# Sheet1.net
KiCad netlist of a schematic drawn in Altium Designer
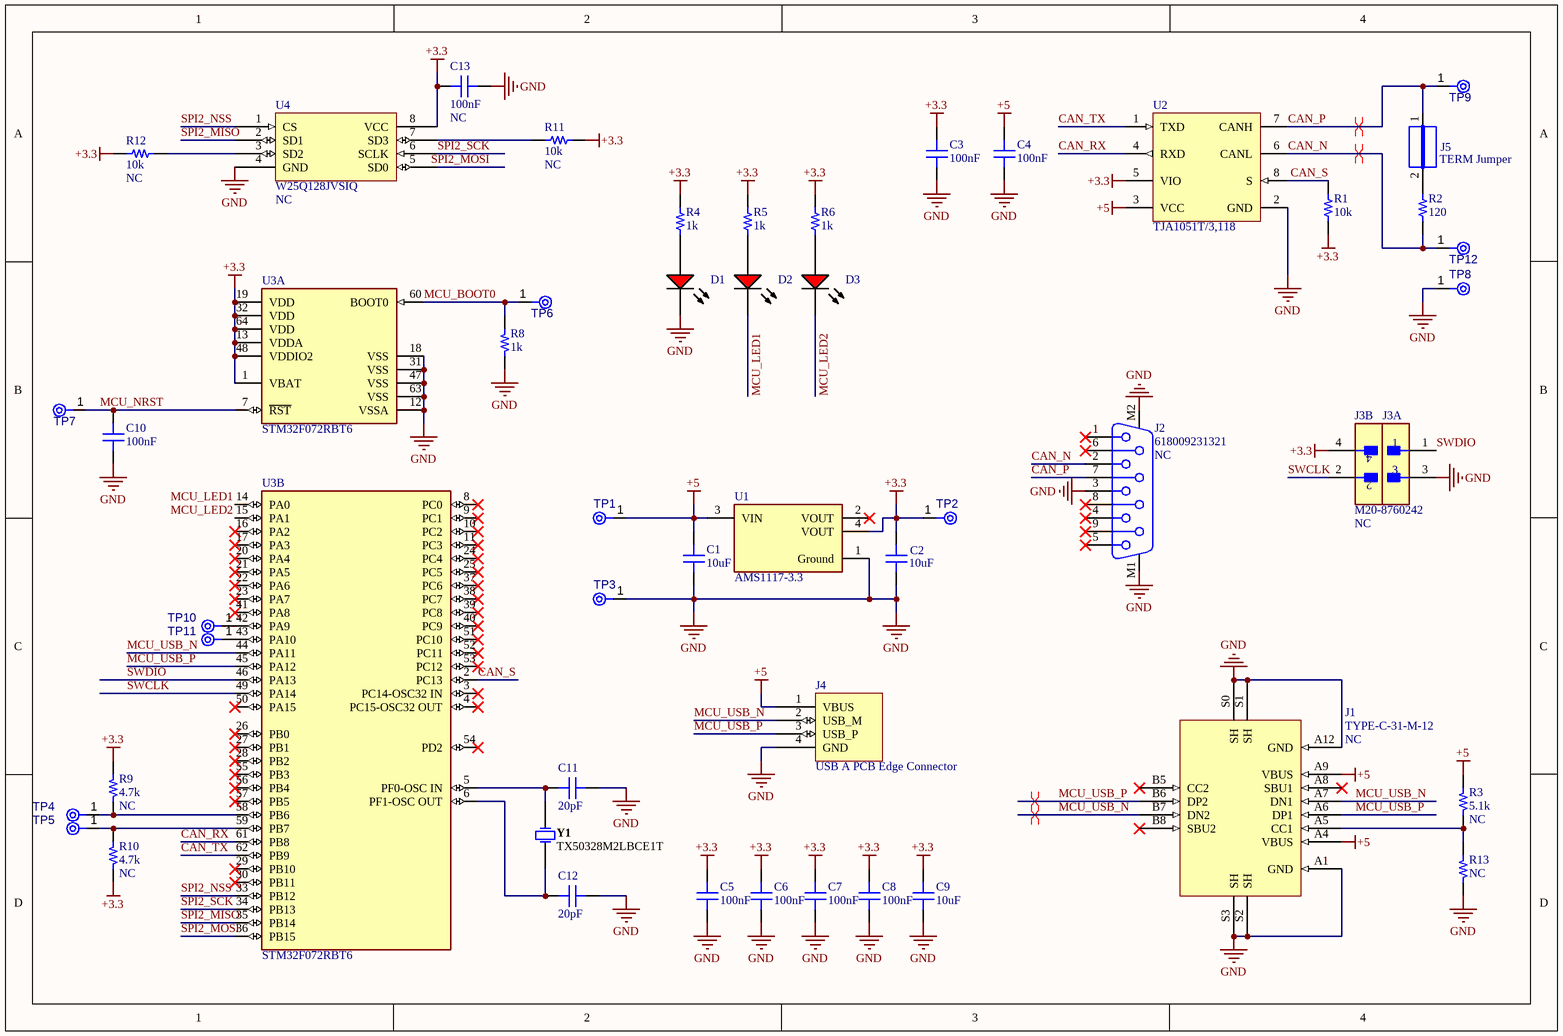
[diagram p0: Sheet1.SchDoc]

(export (version "E")
  (design (tool "Eeschema 10.0.6"))
  (components
    (comp (ref "C1")
      (value "10uF")
      (footprint "CAPC0603(1608)100_L")
      (description "Generic Capacitor")
      (fields (field (name "Comment") "Capacitor"))
      (libsource (lib "OTH Regensburg Ostbayerische Technische Hochschule Regensburg") (part "CAPACITOR"))
    )
    (comp (ref "C2")
      (value "10uF")
      (footprint "CAPC0603(1608)100_L")
      (description "Generic Capacitor")
      (fields (field (name "Comment") "Capacitor"))
      (libsource (lib "OTH Regensburg Ostbayerische Technische Hochschule Regensburg") (part "CAPACITOR"))
    )
    (comp (ref "C3")
      (value "100nF")
      (footprint "CAPC0402(1005)33_L")
      (description "Generic Capacitor")
      (fields (field (name "Comment") "Capacitor"))
      (libsource (lib "OTH Regensburg Ostbayerische Technische Hochschule Regensburg") (part "CAPACITOR"))
    )
    (comp (ref "C4")
      (value "100nF")
      (footprint "CAPC0402(1005)33_L")
      (description "Generic Capacitor")
      (fields (field (name "Comment") "Capacitor"))
      (libsource (lib "OTH Regensburg Ostbayerische Technische Hochschule Regensburg") (part "CAPACITOR"))
    )
    (comp (ref "C5")
      (value "100nF")
      (footprint "CAPC0402(1005)33_L")
      (description "Generic Capacitor")
      (fields (field (name "Comment") "Capacitor"))
      (libsource (lib "OTH Regensburg Ostbayerische Technische Hochschule Regensburg") (part "CAPACITOR"))
    )
    (comp (ref "C6")
      (value "100nF")
      (footprint "CAPC0402(1005)33_L")
      (description "Generic Capacitor")
      (fields (field (name "Comment") "Capacitor"))
      (libsource (lib "OTH Regensburg Ostbayerische Technische Hochschule Regensburg") (part "CAPACITOR"))
    )
    (comp (ref "C7")
      (value "100nF")
      (footprint "CAPC0402(1005)33_L")
      (description "Generic Capacitor")
      (fields (field (name "Comment") "Capacitor"))
      (libsource (lib "OTH Regensburg Ostbayerische Technische Hochschule Regensburg") (part "CAPACITOR"))
    )
    (comp (ref "C8")
      (value "100nF")
      (footprint "CAPC0402(1005)33_L")
      (description "Generic Capacitor")
      (fields (field (name "Comment") "Capacitor"))
      (libsource (lib "OTH Regensburg Ostbayerische Technische Hochschule Regensburg") (part "CAPACITOR"))
    )
    (comp (ref "C9")
      (value "10uF")
      (footprint "CAPC0603(1608)100_L")
      (description "Generic Capacitor")
      (fields (field (name "Comment") "Capacitor"))
      (libsource (lib "OTH Regensburg Ostbayerische Technische Hochschule Regensburg") (part "CAPACITOR"))
    )
    (comp (ref "C10")
      (value "100nF")
      (footprint "CAPC0402(1005)33_L")
      (description "Generic Capacitor")
      (fields (field (name "Comment") "Capacitor"))
      (libsource (lib "OTH Regensburg Ostbayerische Technische Hochschule Regensburg") (part "CAPACITOR"))
    )
    (comp (ref "C11")
      (value "20pF")
      (footprint "CAPC0402(1005)33_L")
      (description "Generic Capacitor")
      (fields (field (name "Comment") "Capacitor"))
      (libsource (lib "OTH Regensburg Ostbayerische Technische Hochschule Regensburg") (part "CAPACITOR"))
    )
    (comp (ref "C12")
      (value "20pF")
      (footprint "CAPC0402(1005)33_L")
      (description "Generic Capacitor")
      (fields (field (name "Comment") "Capacitor"))
      (libsource (lib "OTH Regensburg Ostbayerische Technische Hochschule Regensburg") (part "CAPACITOR"))
    )
    (comp (ref "C13")
      (value "100nF")
      (footprint "CAPC0402(1005)33_L")
      (description "Generic Capacitor")
      (fields (field (name "NOT POPULATED") "NC") (field (name "Comment") "Capacitor"))
      (libsource (lib "OTH Regensburg Ostbayerische Technische Hochschule Regensburg") (part "CAPACITOR"))
    )
    (comp (ref "D1")
      (value "TLMS1100-GS08")
      (footprint "VISH-TLMX1100_V")
      (description "LED, RED, 2.1 V, -40 to 100 degC, 2-Pin SMD (0603), RoHS, Tape and Reel")
      (fields (field (name "TOLERANCE") "5%"))
      (libsource (lib "Altium Content Vault") (part "LED-RED-AK-2"))
    )
    (comp (ref "D2")
      (value "TLMS1100-GS08")
      (footprint "VISH-TLMX1100_V")
      (description "LED, RED, 2.1 V, -40 to 100 degC, 2-Pin SMD (0603), RoHS, Tape and Reel")
      (fields (field (name "TOLERANCE") "5%"))
      (libsource (lib "Altium Content Vault") (part "LED-RED-AK-2"))
    )
    (comp (ref "D3")
      (value "TLMS1100-GS08")
      (footprint "VISH-TLMX1100_V")
      (description "LED, RED, 2.1 V, -40 to 100 degC, 2-Pin SMD (0603), RoHS, Tape and Reel")
      (fields (field (name "TOLERANCE") "5%"))
      (libsource (lib "Altium Content Vault") (part "LED-RED-AK-2"))
    )
    (comp (ref "J1")
      (value "TYPE-C-31-M-12")
      (footprint "TYPE-C-31-M-12-Footprint-1")
      (description "USB Type C USB 2.0")
      (fields (field (name "NOT POPULATED") "NC"))
      (libsource (lib "OTH Regensburg Ostbayerische Technische Hochschule Regensburg") (part "TYPE-C-31-M-12-Symbol-1"))
    )
    (comp (ref "J2")
      (value "618009231321")
      (footprint "618009231321")
      (fields (field (name "NOT POPULATED") "NC"))
      (libsource (lib "Altium Content Vault") (part "D-Sub_Female_09p"))
    )
    (comp (ref "J3")
      (value "M20-8760242")
      (footprint "FP-M20-8760242-MFG")
      (description "CONN HEADER SMD 4POS 2.54MM")
      (fields (field (name "NOT POPULATED") "NC"))
      (libsource (lib "Altium Content Vault") (part "1621473add15499e993d6bbd36d0f06"))
    )
    (comp (ref "J4")
      (value "USB A PCB Edge Connector")
      (footprint "USB A PCB Edge Connector-Footprint-1")
      (libsource (lib "OTH Regensburg Ostbayerische Technische Hochschule Regensburg") (part "USB A PCB Edge Connector-Symbol-1"))
    )
    (comp (ref "J5")
      (value "JUMPER")
      (footprint "JUMPER")
      (fields (field (name "NOT POPULATED") "TERM Jumper"))
      (libsource (lib "OTH Regensburg Ostbayerische Technische Hochschule Regensburg") (part "JUMPER"))
    )
    (comp (ref "R1")
      (value "10k")
      (footprint "RESC0402(1005)_L")
      (description "Generic Resistor")
      (fields (field (name "Comment") "Resistor"))
      (libsource (lib "OTH Regensburg Ostbayerische Technische Hochschule Regensburg") (part "RESISTOR"))
    )
    (comp (ref "R2")
      (value "120")
      (footprint "RESC0603(1608)_L")
      (description "Generic Resistor")
      (fields (field (name "Comment") "Resistor"))
      (libsource (lib "OTH Regensburg Ostbayerische Technische Hochschule Regensburg") (part "RESISTOR"))
    )
    (comp (ref "R3")
      (value "5.1k")
      (footprint "RESC0603(1608)_L")
      (description "Generic Resistor")
      (fields (field (name "NOT POPULATED") "NC") (field (name "Comment") "Resistor"))
      (libsource (lib "OTH Regensburg Ostbayerische Technische Hochschule Regensburg") (part "RESISTOR"))
    )
    (comp (ref "R4")
      (value "1k")
      (footprint "RESC0402(1005)_L")
      (description "Generic Resistor")
      (fields (field (name "Comment") "Resistor"))
      (libsource (lib "OTH Regensburg Ostbayerische Technische Hochschule Regensburg") (part "RESISTOR"))
    )
    (comp (ref "R5")
      (value "1k")
      (footprint "RESC0402(1005)_L")
      (description "Generic Resistor")
      (fields (field (name "Comment") "Resistor"))
      (libsource (lib "OTH Regensburg Ostbayerische Technische Hochschule Regensburg") (part "RESISTOR"))
    )
    (comp (ref "R6")
      (value "1k")
      (footprint "RESC0402(1005)_L")
      (description "Generic Resistor")
      (fields (field (name "Comment") "Resistor"))
      (libsource (lib "OTH Regensburg Ostbayerische Technische Hochschule Regensburg") (part "RESISTOR"))
    )
    (comp (ref "R8")
      (value "1k")
      (footprint "RESC0402(1005)_L")
      (description "Generic Resistor")
      (fields (field (name "Comment") "Resistor"))
      (libsource (lib "OTH Regensburg Ostbayerische Technische Hochschule Regensburg") (part "RESISTOR"))
    )
    (comp (ref "R9")
      (value "4.7k")
      (footprint "RESC0603(1608)_L")
      (description "Generic Resistor")
      (fields (field (name "NOT POPULATED") "NC") (field (name "Comment") "Resistor"))
      (libsource (lib "OTH Regensburg Ostbayerische Technische Hochschule Regensburg") (part "RESISTOR"))
    )
    (comp (ref "R10")
      (value "4.7k")
      (footprint "RESC0603(1608)_L")
      (description "Generic Resistor")
      (fields (field (name "NOT POPULATED") "NC") (field (name "Comment") "Resistor"))
      (libsource (lib "OTH Regensburg Ostbayerische Technische Hochschule Regensburg") (part "RESISTOR"))
    )
    (comp (ref "R11")
      (value "10k")
      (footprint "RESC0402(1005)_L")
      (description "Generic Resistor")
      (fields (field (name "NOT POPULATED") "NC") (field (name "Comment") "Resistor"))
      (libsource (lib "OTH Regensburg Ostbayerische Technische Hochschule Regensburg") (part "RESISTOR"))
    )
    (comp (ref "R12")
      (value "10k")
      (footprint "RESC0402(1005)_L")
      (description "Generic Resistor")
      (fields (field (name "NOT POPULATED") "NC") (field (name "Comment") "Resistor"))
      (libsource (lib "OTH Regensburg Ostbayerische Technische Hochschule Regensburg") (part "RESISTOR"))
    )
    (comp (ref "R13")
      (value "Resistor")
      (footprint "RESC0603(1608)_L")
      (description "Generic Resistor")
      (fields (field (name "NOT POPULATED") "NC"))
      (libsource (lib "OTH Regensburg Ostbayerische Technische Hochschule Regensburg") (part "RESISTOR"))
    )
    (comp (ref "TP1")
      (value "Test Point")
      (footprint "New footprint 1")
      (libsource (lib "OTH Regensburg Ostbayerische Technische Hochschule Regensburg") (part "CMP-001-0001-4"))
    )
    (comp (ref "TP2")
      (value "Test Point")
      (footprint "New footprint 1")
      (libsource (lib "OTH Regensburg Ostbayerische Technische Hochschule Regensburg") (part "CMP-001-0001-4"))
    )
    (comp (ref "TP3")
      (value "Test Point")
      (footprint "New footprint 1")
      (libsource (lib "OTH Regensburg Ostbayerische Technische Hochschule Regensburg") (part "CMP-001-0001-4"))
    )
    (comp (ref "TP4")
      (value "Test Point")
      (footprint "New footprint 1")
      (libsource (lib "OTH Regensburg Ostbayerische Technische Hochschule Regensburg") (part "CMP-001-0001-4"))
    )
    (comp (ref "TP5")
      (value "Test Point")
      (footprint "New footprint 1")
      (libsource (lib "OTH Regensburg Ostbayerische Technische Hochschule Regensburg") (part "CMP-001-0001-4"))
    )
    (comp (ref "TP6")
      (value "Test Point")
      (footprint "New footprint 1")
      (libsource (lib "OTH Regensburg Ostbayerische Technische Hochschule Regensburg") (part "CMP-001-0001-4"))
    )
    (comp (ref "TP7")
      (value "Test Point")
      (footprint "New footprint 1")
      (libsource (lib "OTH Regensburg Ostbayerische Technische Hochschule Regensburg") (part "CMP-001-0001-4"))
    )
    (comp (ref "TP8")
      (value "Test Point")
      (footprint "New footprint 1")
      (libsource (lib "OTH Regensburg Ostbayerische Technische Hochschule Regensburg") (part "CMP-001-0001-4"))
    )
    (comp (ref "TP9")
      (value "Test Point")
      (footprint "New footprint 1")
      (libsource (lib "OTH Regensburg Ostbayerische Technische Hochschule Regensburg") (part "CMP-001-0001-4"))
    )
    (comp (ref "TP10")
      (value "Test Point")
      (footprint "New footprint 1")
      (libsource (lib "OTH Regensburg Ostbayerische Technische Hochschule Regensburg") (part "CMP-001-0001-4"))
    )
    (comp (ref "TP11")
      (value "Test Point")
      (footprint "New footprint 1")
      (libsource (lib "OTH Regensburg Ostbayerische Technische Hochschule Regensburg") (part "CMP-001-0001-4"))
    )
    (comp (ref "TP12")
      (value "Test Point")
      (footprint "New footprint 1")
      (libsource (lib "OTH Regensburg Ostbayerische Technische Hochschule Regensburg") (part "CMP-001-0001-4"))
    )
    (comp (ref "U1")
      (value "AMS1117-3.3")
      (footprint "FP-AMS1117-IPC_A")
      (description "LDO Voltage Regulators 1A, 3.3V")
      (fields
        (field (name "OCTOPART") "https://octopart.com/ams1117-3.3-advanced+monolithic+systems-25899300")
        (field (name "MANUFACTURER") "Advanced Monolithic Systems")
      )
      (libsource (lib "Altium Content Vault") (part "8bdbb5f8e77002000e30dd2845d0354"))
    )
    (comp (ref "U2")
      (value "TJA1051T/3,118")
      (footprint "NXP-SOIC-8_L")
      (description "High-Speed CAN Transceiver, 3 to 5 V, 8-Pin SOIC (SOT96-1), RoHS, Tape and Reel")
      (fields (field (name "MANUFACTURER") "NXP"))
      (libsource (lib "Altium Content Vault") (part "NXP-TJA1051T_3-SOIC-8"))
    )
    (comp (ref "U3")
      (value "STM32F072RBT6")
      (footprint "FP-LQFP64-5W-MFG")
      (description "IC MCU 32BIT 128KB FLASH 64LQFP")
      (fields
        (field (name "MANUFACTURER") "STMicroelectronics")
        (field (name "OCTOPART") "https://octopart.com/stm32f072rbt6-stmicroelectronics-34084849")
      )
      (libsource (lib "Altium Content Vault") (part "2898ff2af3f565795d3b9648bb0e0e1"))
    )
    (comp (ref "U4")
      (value "W25Q128JVSIQ")
      (footprint "WINBOND SOIC-8 208MIL WIDE")
      (description "Flash, 16MX8, PDSO8")
      (fields (field (name "NOT POPULATED") "NC"))
      (libsource (lib "OTH Regensburg Ostbayerische Technische Hochschule Regensburg") (part "W25Q128JVSIQ-Symbol-1"))
    )
    (comp (ref "Y1")
      (value "TX50328M2LBCE1T")
      (footprint "FP-ABM3-MFG")
      (libsource (lib "OTH Regensburg Ostbayerische Technische Hochschule Regensburg") (part "XTAL-2"))
    )
  )
  (nets
    (net (code "1") (name "+3.3") (class "Default")
      (node (ref "C13") (pin "2") (pinfunction "2_2") (pintype "passive"))
      (node (ref "C2") (pin "2") (pinfunction "2_2") (pintype "passive"))
      (node (ref "C3") (pin "2") (pinfunction "2_2") (pintype "passive"))
      (node (ref "C5") (pin "2") (pinfunction "2_2") (pintype "passive"))
      (node (ref "C6") (pin "2") (pinfunction "2_2") (pintype "passive"))
      (node (ref "C7") (pin "2") (pinfunction "2_2") (pintype "passive"))
      (node (ref "C8") (pin "2") (pinfunction "2_2") (pintype "passive"))
      (node (ref "C9") (pin "2") (pinfunction "2_2") (pintype "passive"))
      (node (ref "J3") (pin "4") (pinfunction "4_4") (pintype "passive"))
      (node (ref "R1") (pin "2") (pinfunction "2_2") (pintype "passive"))
      (node (ref "R10") (pin "1") (pinfunction "1_1") (pintype "passive"))
      (node (ref "R11") (pin "2") (pinfunction "2_2") (pintype "passive"))
      (node (ref "R12") (pin "1") (pinfunction "1_1") (pintype "passive"))
      (node (ref "R4") (pin "2") (pinfunction "2_2") (pintype "passive"))
      (node (ref "R5") (pin "2") (pinfunction "2_2") (pintype "passive"))
      (node (ref "R6") (pin "2") (pinfunction "2_2") (pintype "passive"))
      (node (ref "R9") (pin "2") (pinfunction "2_2") (pintype "passive"))
      (node (ref "TP2") (pin "1") (pinfunction "TP_1") (pintype "passive"))
      (node (ref "U1") (pin "4") (pinfunction "VOUT_4") (pintype "passive"))
      (node (ref "U2") (pin "5") (pinfunction "VIO_5") (pintype "power_in"))
      (node (ref "U3") (pin "1") (pinfunction "VBAT_1") (pintype "power_in"))
      (node (ref "U3") (pin "13") (pinfunction "VDDA_13") (pintype "power_in"))
      (node (ref "U3") (pin "19") (pinfunction "VDD_19") (pintype "power_in"))
      (node (ref "U3") (pin "32") (pinfunction "VDD_32") (pintype "power_in"))
      (node (ref "U3") (pin "48") (pinfunction "VDDIO2_48") (pintype "power_in"))
      (node (ref "U3") (pin "64") (pinfunction "VDD_64") (pintype "power_in"))
      (node (ref "U4") (pin "8") (pinfunction "VCC_8") (pintype "power_in"))
    )
    (net (code "2") (name "+5") (class "Default")
      (node (ref "C1") (pin "2") (pinfunction "2_2") (pintype "passive"))
      (node (ref "C4") (pin "2") (pinfunction "2_2") (pintype "passive"))
      (node (ref "J1") (pin "A4") (pinfunction "VBUS_A4") (pintype "input"))
      (node (ref "J1") (pin "A9") (pinfunction "VBUS_A9") (pintype "input"))
      (node (ref "J4") (pin "1") (pinfunction "VBUS_1") (pintype "power_in"))
      (node (ref "R3") (pin "1") (pinfunction "1_1") (pintype "passive"))
      (node (ref "TP1") (pin "1") (pinfunction "TP_1") (pintype "passive"))
      (node (ref "U1") (pin "3") (pinfunction "VIN_3") (pintype "power_in"))
      (node (ref "U2") (pin "3") (pinfunction "VCC_3") (pintype "power_in"))
    )
    (net (code "3") (name "/CAN_N") (class "Default")
      (node (ref "J2") (pin "2") (pinfunction "2_2") (pintype "passive"))
      (node (ref "R2") (pin "2") (pinfunction "2_2") (pintype "passive"))
      (node (ref "TP12") (pin "1") (pinfunction "TP_1") (pintype "passive"))
      (node (ref "U2") (pin "6") (pinfunction "CANL_6") (pintype "passive"))
    )
    (net (code "4") (name "/CAN_P") (class "Default")
      (node (ref "J2") (pin "7") (pinfunction "7_7") (pintype "passive"))
      (node (ref "J5") (pin "1") (pinfunction "1_1") (pintype "passive"))
      (node (ref "TP9") (pin "1") (pinfunction "TP_1") (pintype "passive"))
      (node (ref "U2") (pin "7") (pinfunction "CANH_7") (pintype "passive"))
    )
    (net (code "5") (name "/CAN_RX") (class "Default")
      (node (ref "U2") (pin "4") (pinfunction "RXD_4") (pintype "output"))
      (node (ref "U3") (pin "61") (pinfunction "PB8_61") (pintype "bidirectional"))
    )
    (net (code "6") (name "/CAN_S") (class "Default")
      (node (ref "R1") (pin "1") (pinfunction "1_1") (pintype "passive"))
      (node (ref "U2") (pin "8") (pinfunction "S_8") (pintype "input"))
      (node (ref "U3") (pin "2") (pinfunction "PC13_2") (pintype "bidirectional"))
    )
    (net (code "7") (name "/CAN_TX") (class "Default")
      (node (ref "U2") (pin "1") (pinfunction "TXD_1") (pintype "input"))
      (node (ref "U3") (pin "62") (pinfunction "PB9_62") (pintype "bidirectional"))
    )
    (net (code "8") (name "/MCU_BOOT0") (class "Default")
      (node (ref "R8") (pin "2") (pinfunction "2_2") (pintype "passive"))
      (node (ref "TP6") (pin "1") (pinfunction "TP_1") (pintype "passive"))
      (node (ref "U3") (pin "60") (pinfunction "BOOT0_60") (pintype "input"))
    )
    (net (code "9") (name "/MCU_LED1") (class "Default")
      (node (ref "D2") (pin "2") (pinfunction "K_2") (pintype "passive"))
      (node (ref "U3") (pin "14") (pinfunction "PA0_14") (pintype "bidirectional"))
    )
    (net (code "10") (name "/MCU_LED2") (class "Default")
      (node (ref "D3") (pin "2") (pinfunction "K_2") (pintype "passive"))
      (node (ref "U3") (pin "15") (pinfunction "PA1_15") (pintype "bidirectional"))
    )
    (net (code "11") (name "/MCU_NRST") (class "Default")
      (node (ref "C10") (pin "2") (pinfunction "2_2") (pintype "passive"))
      (node (ref "TP7") (pin "1") (pinfunction "TP_1") (pintype "passive"))
      (node (ref "U3") (pin "7") (pinfunction "~{RST}_7") (pintype "bidirectional"))
    )
    (net (code "12") (name "/MCU_USB_N") (class "Default")
      (node (ref "J1") (pin "A7") (pinfunction "DN1_A7") (pintype "input"))
      (node (ref "J1") (pin "B7") (pinfunction "DN2_B7") (pintype "input"))
      (node (ref "J4") (pin "2") (pinfunction "USB_M_2") (pintype "bidirectional"))
      (node (ref "U3") (pin "44") (pinfunction "PA11_44") (pintype "bidirectional"))
    )
    (net (code "13") (name "/MCU_USB_P") (class "Default")
      (node (ref "J1") (pin "A6") (pinfunction "DP1_A6") (pintype "input"))
      (node (ref "J1") (pin "B6") (pinfunction "DP2_B6") (pintype "input"))
      (node (ref "J4") (pin "3") (pinfunction "USB_P_3") (pintype "bidirectional"))
      (node (ref "U3") (pin "45") (pinfunction "PA12_45") (pintype "bidirectional"))
    )
    (net (code "14") (name "/SPI2_MISO") (class "Default")
      (node (ref "U3") (pin "35") (pinfunction "PB14_35") (pintype "bidirectional"))
      (node (ref "U4") (pin "2") (pinfunction "SD1_2") (pintype "bidirectional"))
    )
    (net (code "15") (name "/SPI2_MOSI") (class "Default")
      (node (ref "U3") (pin "36") (pinfunction "PB15_36") (pintype "bidirectional"))
      (node (ref "U4") (pin "5") (pinfunction "SD0_5") (pintype "bidirectional"))
    )
    (net (code "16") (name "/SPI2_NSS") (class "Default")
      (node (ref "U3") (pin "33") (pinfunction "PB12_33") (pintype "bidirectional"))
      (node (ref "U4") (pin "1") (pinfunction "CS_1") (pintype "input"))
    )
    (net (code "17") (name "/SPI2_SCK") (class "Default")
      (node (ref "U3") (pin "34") (pinfunction "PB13_34") (pintype "bidirectional"))
      (node (ref "U4") (pin "6") (pinfunction "SCLK_6") (pintype "input"))
    )
    (net (code "18") (name "/SWCLK") (class "Default")
      (node (ref "J3") (pin "2") (pinfunction "2_2") (pintype "passive"))
      (node (ref "U3") (pin "49") (pinfunction "PA14_49") (pintype "bidirectional"))
    )
    (net (code "19") (name "/SWDIO") (class "Default")
      (node (ref "J3") (pin "1") (pinfunction "1_1") (pintype "passive"))
      (node (ref "U3") (pin "46") (pinfunction "PA13_46") (pintype "bidirectional"))
    )
    (net (code "20") (name "GND") (class "Default")
      (node (ref "C1") (pin "1") (pinfunction "1_1") (pintype "passive"))
      (node (ref "C10") (pin "1") (pinfunction "1_1") (pintype "passive"))
      (node (ref "C11") (pin "1") (pinfunction "1_1") (pintype "passive"))
      (node (ref "C12") (pin "1") (pinfunction "1_1") (pintype "passive"))
      (node (ref "C13") (pin "1") (pinfunction "1_1") (pintype "passive"))
      (node (ref "C2") (pin "1") (pinfunction "1_1") (pintype "passive"))
      (node (ref "C3") (pin "1") (pinfunction "1_1") (pintype "passive"))
      (node (ref "C4") (pin "1") (pinfunction "1_1") (pintype "passive"))
      (node (ref "C5") (pin "1") (pinfunction "1_1") (pintype "passive"))
      (node (ref "C6") (pin "1") (pinfunction "1_1") (pintype "passive"))
      (node (ref "C7") (pin "1") (pinfunction "1_1") (pintype "passive"))
      (node (ref "C8") (pin "1") (pinfunction "1_1") (pintype "passive"))
      (node (ref "C9") (pin "1") (pinfunction "1_1") (pintype "passive"))
      (node (ref "D1") (pin "2") (pinfunction "K_2") (pintype "passive"))
      (node (ref "J1") (pin "A1") (pinfunction "GND_A1") (pintype "input"))
      (node (ref "J1") (pin "A12") (pinfunction "GND_A12") (pintype "input"))
      (node (ref "J1") (pin "S0") (pinfunction "SH_S0") (pintype "passive"))
      (node (ref "J1") (pin "S1") (pinfunction "SH_S1") (pintype "passive"))
      (node (ref "J1") (pin "S2") (pinfunction "SH_S2") (pintype "passive"))
      (node (ref "J1") (pin "S3") (pinfunction "SH_S3") (pintype "passive"))
      (node (ref "J2") (pin "3") (pinfunction "3_3") (pintype "passive"))
      (node (ref "J2") (pin "M1") (pinfunction "M1_M1") (pintype "passive"))
      (node (ref "J2") (pin "M2") (pinfunction "M2_M2") (pintype "passive"))
      (node (ref "J3") (pin "3") (pinfunction "3_3") (pintype "passive"))
      (node (ref "J4") (pin "4") (pinfunction "GND_4") (pintype "power_in"))
      (node (ref "R13") (pin "1") (pinfunction "1_1") (pintype "passive"))
      (node (ref "R8") (pin "1") (pinfunction "1_1") (pintype "passive"))
      (node (ref "TP3") (pin "1") (pinfunction "TP_1") (pintype "passive"))
      (node (ref "TP8") (pin "1") (pinfunction "TP_1") (pintype "passive"))
      (node (ref "U1") (pin "1") (pinfunction "Ground_1") (pintype "power_in"))
      (node (ref "U2") (pin "2") (pinfunction "GND_2") (pintype "power_in"))
      (node (ref "U3") (pin "12") (pinfunction "VSSA_12") (pintype "power_in"))
      (node (ref "U3") (pin "18") (pinfunction "VSS_18") (pintype "power_in"))
      (node (ref "U3") (pin "31") (pinfunction "VSS_31") (pintype "power_in"))
      (node (ref "U3") (pin "47") (pinfunction "VSS_47") (pintype "power_in"))
      (node (ref "U3") (pin "63") (pinfunction "VSS_63") (pintype "power_in"))
      (node (ref "U4") (pin "4") (pinfunction "GND_4") (pintype "power_in"))
    )
    (net (code "21") (name "Net-(D1-A)") (class "Default")
      (node (ref "D1") (pin "1") (pinfunction "A_1") (pintype "passive"))
      (node (ref "R4") (pin "1") (pinfunction "1_1") (pintype "passive"))
    )
    (net (code "22") (name "Net-(D2-A)") (class "Default")
      (node (ref "D2") (pin "1") (pinfunction "A_1") (pintype "passive"))
      (node (ref "R5") (pin "1") (pinfunction "1_1") (pintype "passive"))
    )
    (net (code "23") (name "Net-(D3-A)") (class "Default")
      (node (ref "D3") (pin "1") (pinfunction "A_1") (pintype "passive"))
      (node (ref "R6") (pin "1") (pinfunction "1_1") (pintype "passive"))
    )
    (net (code "24") (name "Net-(J1-CC1)") (class "Default")
      (node (ref "J1") (pin "A5") (pinfunction "CC1_A5") (pintype "input"))
      (node (ref "R13") (pin "2") (pinfunction "2_2") (pintype "passive"))
      (node (ref "R3") (pin "2") (pinfunction "2_2") (pintype "passive"))
    )
    (net (code "25") (name "Net-(J5-Pad2)") (class "Default")
      (node (ref "J5") (pin "2") (pinfunction "2_2") (pintype "passive"))
      (node (ref "R2") (pin "1") (pinfunction "1_1") (pintype "passive"))
    )
    (net (code "26") (name "Net-(TP4-TP)") (class "Default")
      (node (ref "R9") (pin "1") (pinfunction "1_1") (pintype "passive"))
      (node (ref "TP4") (pin "1") (pinfunction "TP_1") (pintype "passive"))
      (node (ref "U3") (pin "58") (pinfunction "PB6_58") (pintype "bidirectional"))
    )
    (net (code "27") (name "Net-(TP5-TP)") (class "Default")
      (node (ref "R10") (pin "2") (pinfunction "2_2") (pintype "passive"))
      (node (ref "TP5") (pin "1") (pinfunction "TP_1") (pintype "passive"))
      (node (ref "U3") (pin "59") (pinfunction "PB7_59") (pintype "bidirectional"))
    )
    (net (code "28") (name "Net-(TP10-TP)") (class "Default")
      (node (ref "TP10") (pin "1") (pinfunction "TP_1") (pintype "passive"))
      (node (ref "U3") (pin "42") (pinfunction "PA9_42") (pintype "bidirectional"))
    )
    (net (code "29") (name "Net-(TP11-TP)") (class "Default")
      (node (ref "TP11") (pin "1") (pinfunction "TP_1") (pintype "passive"))
      (node (ref "U3") (pin "43") (pinfunction "PA10_43") (pintype "bidirectional"))
    )
    (net (code "30") (name "Net-(U3B-PF0-OSC_IN)") (class "Default")
      (node (ref "C11") (pin "2") (pinfunction "2_2") (pintype "passive"))
      (node (ref "U3") (pin "5") (pinfunction "PF0-OSC_IN_5") (pintype "bidirectional"))
      (node (ref "Y1") (pin "2") (pinfunction "2_2") (pintype "passive"))
    )
    (net (code "31") (name "Net-(U3B-PF1-OSC_OUT)") (class "Default")
      (node (ref "C12") (pin "2") (pinfunction "2_2") (pintype "passive"))
      (node (ref "U3") (pin "6") (pinfunction "PF1-OSC_OUT_6") (pintype "bidirectional"))
      (node (ref "Y1") (pin "1") (pinfunction "1_1") (pintype "passive"))
    )
    (net (code "32") (name "Net-(U4-SD2)") (class "Default")
      (node (ref "R12") (pin "2") (pinfunction "2_2") (pintype "passive"))
      (node (ref "U4") (pin "3") (pinfunction "SD2_3") (pintype "bidirectional"))
    )
    (net (code "33") (name "Net-(U4-SD3)") (class "Default")
      (node (ref "R11") (pin "1") (pinfunction "1_1") (pintype "passive"))
      (node (ref "U4") (pin "7") (pinfunction "SD3_7") (pintype "bidirectional"))
    )
    (net (code "34") (name "unconnected-(J1-CC2-PadB5)") (class "Default")
      (node (ref "J1") (pin "B5") (pinfunction "CC2_B5") (pintype "input+no_connect"))
    )
    (net (code "35") (name "unconnected-(J1-SBU1-PadA8)") (class "Default")
      (node (ref "J1") (pin "A8") (pinfunction "SBU1_A8") (pintype "input+no_connect"))
    )
    (net (code "36") (name "unconnected-(J1-SBU2-PadB8)") (class "Default")
      (node (ref "J1") (pin "B8") (pinfunction "SBU2_B8") (pintype "input+no_connect"))
    )
    (net (code "37") (name "unconnected-(J2-Pad1)") (class "Default")
      (node (ref "J2") (pin "1") (pinfunction "1_1") (pintype "passive+no_connect"))
    )
    (net (code "38") (name "unconnected-(J2-Pad4)") (class "Default")
      (node (ref "J2") (pin "4") (pinfunction "4_4") (pintype "passive+no_connect"))
    )
    (net (code "39") (name "unconnected-(J2-Pad5)") (class "Default")
      (node (ref "J2") (pin "5") (pinfunction "5_5") (pintype "passive+no_connect"))
    )
    (net (code "40") (name "unconnected-(J2-Pad6)") (class "Default")
      (node (ref "J2") (pin "6") (pinfunction "6_6") (pintype "passive+no_connect"))
    )
    (net (code "41") (name "unconnected-(J2-Pad8)") (class "Default")
      (node (ref "J2") (pin "8") (pinfunction "8_8") (pintype "passive+no_connect"))
    )
    (net (code "42") (name "unconnected-(J2-Pad9)") (class "Default")
      (node (ref "J2") (pin "9") (pinfunction "9_9") (pintype "passive+no_connect"))
    )
    (net (code "43") (name "unconnected-(U1-VOUT-Pad2)") (class "Default")
      (node (ref "U1") (pin "2") (pinfunction "VOUT_2") (pintype "passive+no_connect"))
    )
    (net (code "44") (name "unconnected-(U3B-PA2-Pad16)") (class "Default")
      (node (ref "U3") (pin "16") (pinfunction "PA2_16") (pintype "bidirectional+no_connect"))
    )
    (net (code "45") (name "unconnected-(U3B-PA3-Pad17)") (class "Default")
      (node (ref "U3") (pin "17") (pinfunction "PA3_17") (pintype "bidirectional+no_connect"))
    )
    (net (code "46") (name "unconnected-(U3B-PA4-Pad20)") (class "Default")
      (node (ref "U3") (pin "20") (pinfunction "PA4_20") (pintype "bidirectional+no_connect"))
    )
    (net (code "47") (name "unconnected-(U3B-PA5-Pad21)") (class "Default")
      (node (ref "U3") (pin "21") (pinfunction "PA5_21") (pintype "bidirectional+no_connect"))
    )
    (net (code "48") (name "unconnected-(U3B-PA6-Pad22)") (class "Default")
      (node (ref "U3") (pin "22") (pinfunction "PA6_22") (pintype "bidirectional+no_connect"))
    )
    (net (code "49") (name "unconnected-(U3B-PA7-Pad23)") (class "Default")
      (node (ref "U3") (pin "23") (pinfunction "PA7_23") (pintype "bidirectional+no_connect"))
    )
    (net (code "50") (name "unconnected-(U3B-PA8-Pad41)") (class "Default")
      (node (ref "U3") (pin "41") (pinfunction "PA8_41") (pintype "bidirectional+no_connect"))
    )
    (net (code "51") (name "unconnected-(U3B-PA15-Pad50)") (class "Default")
      (node (ref "U3") (pin "50") (pinfunction "PA15_50") (pintype "bidirectional+no_connect"))
    )
    (net (code "52") (name "unconnected-(U3B-PB0-Pad26)") (class "Default")
      (node (ref "U3") (pin "26") (pinfunction "PB0_26") (pintype "bidirectional+no_connect"))
    )
    (net (code "53") (name "unconnected-(U3B-PB1-Pad27)") (class "Default")
      (node (ref "U3") (pin "27") (pinfunction "PB1_27") (pintype "bidirectional+no_connect"))
    )
    (net (code "54") (name "unconnected-(U3B-PB2-Pad28)") (class "Default")
      (node (ref "U3") (pin "28") (pinfunction "PB2_28") (pintype "bidirectional+no_connect"))
    )
    (net (code "55") (name "unconnected-(U3B-PB3-Pad55)") (class "Default")
      (node (ref "U3") (pin "55") (pinfunction "PB3_55") (pintype "bidirectional+no_connect"))
    )
    (net (code "56") (name "unconnected-(U3B-PB4-Pad56)") (class "Default")
      (node (ref "U3") (pin "56") (pinfunction "PB4_56") (pintype "bidirectional+no_connect"))
    )
    (net (code "57") (name "unconnected-(U3B-PB5-Pad57)") (class "Default")
      (node (ref "U3") (pin "57") (pinfunction "PB5_57") (pintype "bidirectional+no_connect"))
    )
    (net (code "58") (name "unconnected-(U3B-PB10-Pad29)") (class "Default")
      (node (ref "U3") (pin "29") (pinfunction "PB10_29") (pintype "bidirectional+no_connect"))
    )
    (net (code "59") (name "unconnected-(U3B-PB11-Pad30)") (class "Default")
      (node (ref "U3") (pin "30") (pinfunction "PB11_30") (pintype "bidirectional+no_connect"))
    )
    (net (code "60") (name "unconnected-(U3B-PC0-Pad8)") (class "Default")
      (node (ref "U3") (pin "8") (pinfunction "PC0_8") (pintype "bidirectional+no_connect"))
    )
    (net (code "61") (name "unconnected-(U3B-PC1-Pad9)") (class "Default")
      (node (ref "U3") (pin "9") (pinfunction "PC1_9") (pintype "bidirectional+no_connect"))
    )
    (net (code "62") (name "unconnected-(U3B-PC2-Pad10)") (class "Default")
      (node (ref "U3") (pin "10") (pinfunction "PC2_10") (pintype "bidirectional+no_connect"))
    )
    (net (code "63") (name "unconnected-(U3B-PC3-Pad11)") (class "Default")
      (node (ref "U3") (pin "11") (pinfunction "PC3_11") (pintype "bidirectional+no_connect"))
    )
    (net (code "64") (name "unconnected-(U3B-PC4-Pad24)") (class "Default")
      (node (ref "U3") (pin "24") (pinfunction "PC4_24") (pintype "bidirectional+no_connect"))
    )
    (net (code "65") (name "unconnected-(U3B-PC5-Pad25)") (class "Default")
      (node (ref "U3") (pin "25") (pinfunction "PC5_25") (pintype "bidirectional+no_connect"))
    )
    (net (code "66") (name "unconnected-(U3B-PC6-Pad37)") (class "Default")
      (node (ref "U3") (pin "37") (pinfunction "PC6_37") (pintype "bidirectional+no_connect"))
    )
    (net (code "67") (name "unconnected-(U3B-PC7-Pad38)") (class "Default")
      (node (ref "U3") (pin "38") (pinfunction "PC7_38") (pintype "bidirectional+no_connect"))
    )
    (net (code "68") (name "unconnected-(U3B-PC8-Pad39)") (class "Default")
      (node (ref "U3") (pin "39") (pinfunction "PC8_39") (pintype "bidirectional+no_connect"))
    )
    (net (code "69") (name "unconnected-(U3B-PC9-Pad40)") (class "Default")
      (node (ref "U3") (pin "40") (pinfunction "PC9_40") (pintype "bidirectional+no_connect"))
    )
    (net (code "70") (name "unconnected-(U3B-PC10-Pad51)") (class "Default")
      (node (ref "U3") (pin "51") (pinfunction "PC10_51") (pintype "bidirectional+no_connect"))
    )
    (net (code "71") (name "unconnected-(U3B-PC11-Pad52)") (class "Default")
      (node (ref "U3") (pin "52") (pinfunction "PC11_52") (pintype "bidirectional+no_connect"))
    )
    (net (code "72") (name "unconnected-(U3B-PC12-Pad53)") (class "Default")
      (node (ref "U3") (pin "53") (pinfunction "PC12_53") (pintype "bidirectional+no_connect"))
    )
    (net (code "73") (name "unconnected-(U3B-PC14-OSC32_IN-Pad3)") (class "Default")
      (node (ref "U3") (pin "3") (pinfunction "PC14-OSC32_IN_3") (pintype "bidirectional+no_connect"))
    )
    (net (code "74") (name "unconnected-(U3B-PC15-OSC32_OUT-Pad4)") (class "Default")
      (node (ref "U3") (pin "4") (pinfunction "PC15-OSC32_OUT_4") (pintype "bidirectional+no_connect"))
    )
    (net (code "75") (name "unconnected-(U3B-PD2-Pad54)") (class "Default")
      (node (ref "U3") (pin "54") (pinfunction "PD2_54") (pintype "bidirectional+no_connect"))
    )
  )
)
